# Sheet5.net
KiCad netlist of a schematic drawn in Altium Designer
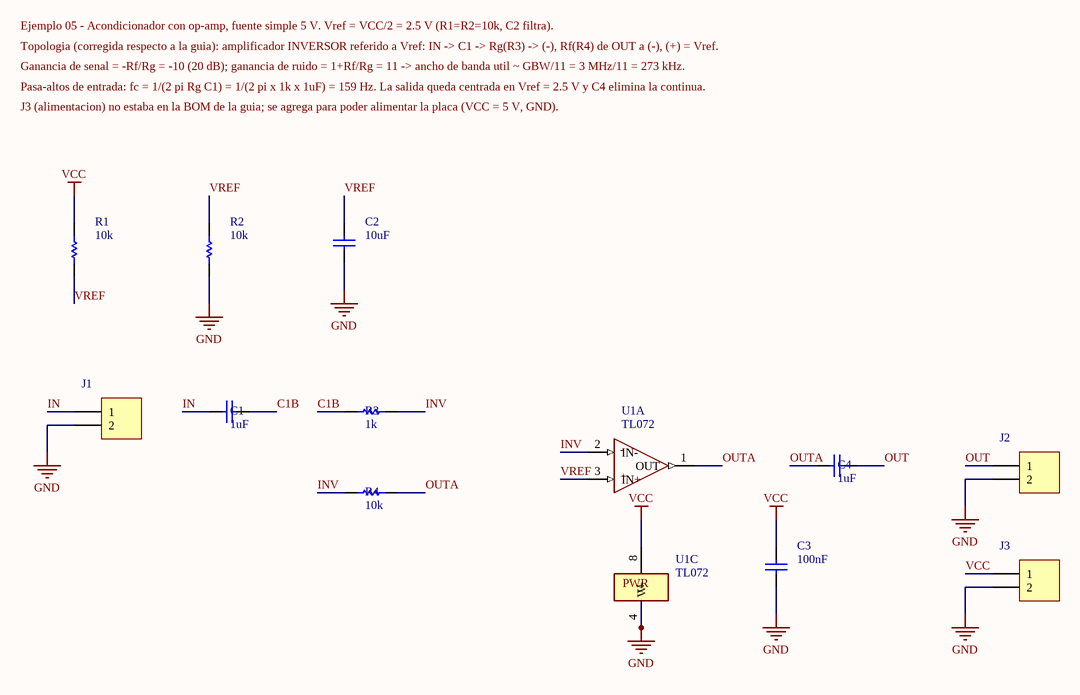
[diagram p0: Sheet5.SchDoc]

(export (version "E")
  (design (tool "Eeschema 10.0.6"))
  (components
    (comp (ref "C1")
      (value "1uF")
      (footprint "RAD-0.3")
      (description "Ceramic capacitor 1uF")
      (fields
        (field (name "MANUFACTURER") "KEMET")
        (field (name "MANUFACTURER PART NUMBER") "C320C105K5R5TA")
        (field (name "PUBLISHER") "Altium Limited")
      )
      (libsource (lib "Miscellaneous Devices") (part "Cap"))
    )
    (comp (ref "C2")
      (value "10uF")
      (footprint "RAD-0.3")
      (description "Ceramic capacitor 10uF")
      (fields
        (field (name "MANUFACTURER") "KEMET")
        (field (name "MANUFACTURER PART NUMBER") "C320C106K3R5TA")
        (field (name "PUBLISHER") "Altium Limited")
      )
      (libsource (lib "Miscellaneous Devices") (part "Cap"))
    )
    (comp (ref "C3")
      (value "100nF")
      (footprint "RAD-0.3")
      (description "Ceramic capacitor 100nF")
      (fields
        (field (name "MANUFACTURER") "KEMET")
        (field (name "MANUFACTURER PART NUMBER") "C320C104K5R5TA")
        (field (name "PUBLISHER") "Altium Limited")
      )
      (libsource (lib "Miscellaneous Devices") (part "Cap"))
    )
    (comp (ref "C4")
      (value "1uF")
      (footprint "RAD-0.3")
      (description "Ceramic capacitor 1uF")
      (fields
        (field (name "MANUFACTURER") "KEMET")
        (field (name "MANUFACTURER PART NUMBER") "C320C105K5R5TA")
        (field (name "PUBLISHER") "Altium Limited")
      )
      (libsource (lib "Miscellaneous Devices") (part "Cap"))
    )
    (comp (ref "J1")
      (value "Header 2")
      (footprint "HDR1X2")
      (description "Header 2 pin 2.54 mm: signal input (IN, GND)")
      (fields
        (field (name "MANUFACTURER") "Generic")
        (field (name "MANUFACTURER PART NUMBER") "Pin header 1x2")
        (field (name "PUBLISHER") "Altium Limited")
      )
      (libsource (lib "Miscellaneous Connectors") (part "Header 2"))
    )
    (comp (ref "J2")
      (value "Header 2")
      (footprint "HDR1X2")
      (description "Header 2 pin 2.54 mm: signal output (OUT, GND)")
      (fields
        (field (name "MANUFACTURER") "Generic")
        (field (name "MANUFACTURER PART NUMBER") "Pin header 1x2")
        (field (name "PUBLISHER") "Altium Limited")
      )
      (libsource (lib "Miscellaneous Connectors") (part "Header 2"))
    )
    (comp (ref "J3")
      (value "Header 2")
      (footprint "HDR1X2")
      (description "Header 2 pin 2.54 mm: supply input (VCC 5 V, GND)")
      (fields
        (field (name "MANUFACTURER") "Generic")
        (field (name "MANUFACTURER PART NUMBER") "Pin header 1x2")
        (field (name "PUBLISHER") "Altium Limited")
      )
      (libsource (lib "Miscellaneous Connectors") (part "Header 2"))
    )
    (comp (ref "R1")
      (value "10k")
      (footprint "AXIAL-0.3")
      (description "Resistor 10k 1/4 W 5%")
      (fields
        (field (name "MANUFACTURER") "Yageo")
        (field (name "MANUFACTURER PART NUMBER") "CFR-25JB-52-10K")
        (field (name "PUBLISHER") "Altium Limited")
      )
      (libsource (lib "Miscellaneous Devices") (part "Res1"))
    )
    (comp (ref "R2")
      (value "10k")
      (footprint "AXIAL-0.3")
      (description "Resistor 10k 1/4 W 5%")
      (fields
        (field (name "MANUFACTURER") "Yageo")
        (field (name "MANUFACTURER PART NUMBER") "CFR-25JB-52-10K")
        (field (name "PUBLISHER") "Altium Limited")
      )
      (libsource (lib "Miscellaneous Devices") (part "Res1"))
    )
    (comp (ref "R3")
      (value "1k")
      (footprint "AXIAL-0.3")
      (description "Resistor 1k 1/4 W 5%")
      (fields
        (field (name "MANUFACTURER") "Yageo")
        (field (name "MANUFACTURER PART NUMBER") "CFR-25JB-52-1K")
        (field (name "PUBLISHER") "Altium Limited")
      )
      (libsource (lib "Miscellaneous Devices") (part "Res1"))
    )
    (comp (ref "R4")
      (value "10k")
      (footprint "AXIAL-0.3")
      (description "Resistor 10k 1/4 W 5%")
      (fields
        (field (name "MANUFACTURER") "Yageo")
        (field (name "MANUFACTURER PART NUMBER") "CFR-25JB-52-10K")
        (field (name "PUBLISHER") "Altium Limited")
      )
      (libsource (lib "Miscellaneous Devices") (part "Res1"))
    )
    (comp (ref "U1")
      (value "TL072")
      (footprint "SO8_N")
      (description "TL072 dual JFET op-amp (A, B) + power part C, SOIC-8")
      (fields
        (field (name "MANUFACTURER") "Texas Instruments")
        (field (name "MANUFACTURER PART NUMBER") "TL072CDR")
      )
      (libsource (lib "") (part "TL072_1"))
    )
  )
  (nets
    (net (code "1") (name "/C1B") (class "Default")
      (node (ref "C1") (pin "2") (pinfunction "2_2") (pintype "passive"))
      (node (ref "R3") (pin "1") (pinfunction "1_1") (pintype "passive"))
    )
    (net (code "2") (name "/IN") (class "Default")
      (node (ref "C1") (pin "1") (pinfunction "1_1") (pintype "passive"))
      (node (ref "J1") (pin "1") (pinfunction "1_1") (pintype "passive"))
    )
    (net (code "3") (name "/INV") (class "Default")
      (node (ref "R3") (pin "2") (pinfunction "2_2") (pintype "passive"))
      (node (ref "R4") (pin "1") (pinfunction "1_1") (pintype "passive"))
      (node (ref "U1") (pin "2") (pinfunction "IN-_2") (pintype "input"))
    )
    (net (code "4") (name "/OUT") (class "Default")
      (node (ref "C4") (pin "2") (pinfunction "2_2") (pintype "passive"))
      (node (ref "J2") (pin "1") (pinfunction "1_1") (pintype "passive"))
    )
    (net (code "5") (name "/OUTA") (class "Default")
      (node (ref "C4") (pin "1") (pinfunction "1_1") (pintype "passive"))
      (node (ref "R4") (pin "2") (pinfunction "2_2") (pintype "passive"))
      (node (ref "U1") (pin "1") (pinfunction "OUT_1") (pintype "output"))
    )
    (net (code "6") (name "/VREF") (class "Default")
      (node (ref "C2") (pin "2") (pinfunction "2_2") (pintype "passive"))
      (node (ref "R1") (pin "1") (pinfunction "1_1") (pintype "passive"))
      (node (ref "R2") (pin "2") (pinfunction "2_2") (pintype "passive"))
      (node (ref "U1") (pin "3") (pinfunction "IN+_3") (pintype "input"))
    )
    (net (code "7") (name "GND") (class "Default")
      (node (ref "C2") (pin "1") (pinfunction "1_1") (pintype "passive"))
      (node (ref "C3") (pin "1") (pinfunction "1_1") (pintype "passive"))
      (node (ref "J1") (pin "2") (pinfunction "2_2") (pintype "passive"))
      (node (ref "J2") (pin "2") (pinfunction "2_2") (pintype "passive"))
      (node (ref "J3") (pin "2") (pinfunction "2_2") (pintype "passive"))
      (node (ref "R2") (pin "1") (pinfunction "1_1") (pintype "passive"))
      (node (ref "U1") (pin "4") (pinfunction "V-_4") (pintype "power_in"))
    )
    (net (code "8") (name "VCC") (class "Default")
      (node (ref "C3") (pin "2") (pinfunction "2_2") (pintype "passive"))
      (node (ref "J3") (pin "1") (pinfunction "1_1") (pintype "passive"))
      (node (ref "R1") (pin "2") (pinfunction "2_2") (pintype "passive"))
      (node (ref "U1") (pin "8") (pinfunction "V+_8") (pintype "power_in"))
    )
  )
)
